# Granny_Safe_Power_Supply.net
KiCad netlist of a schematic drawn in EAGLE
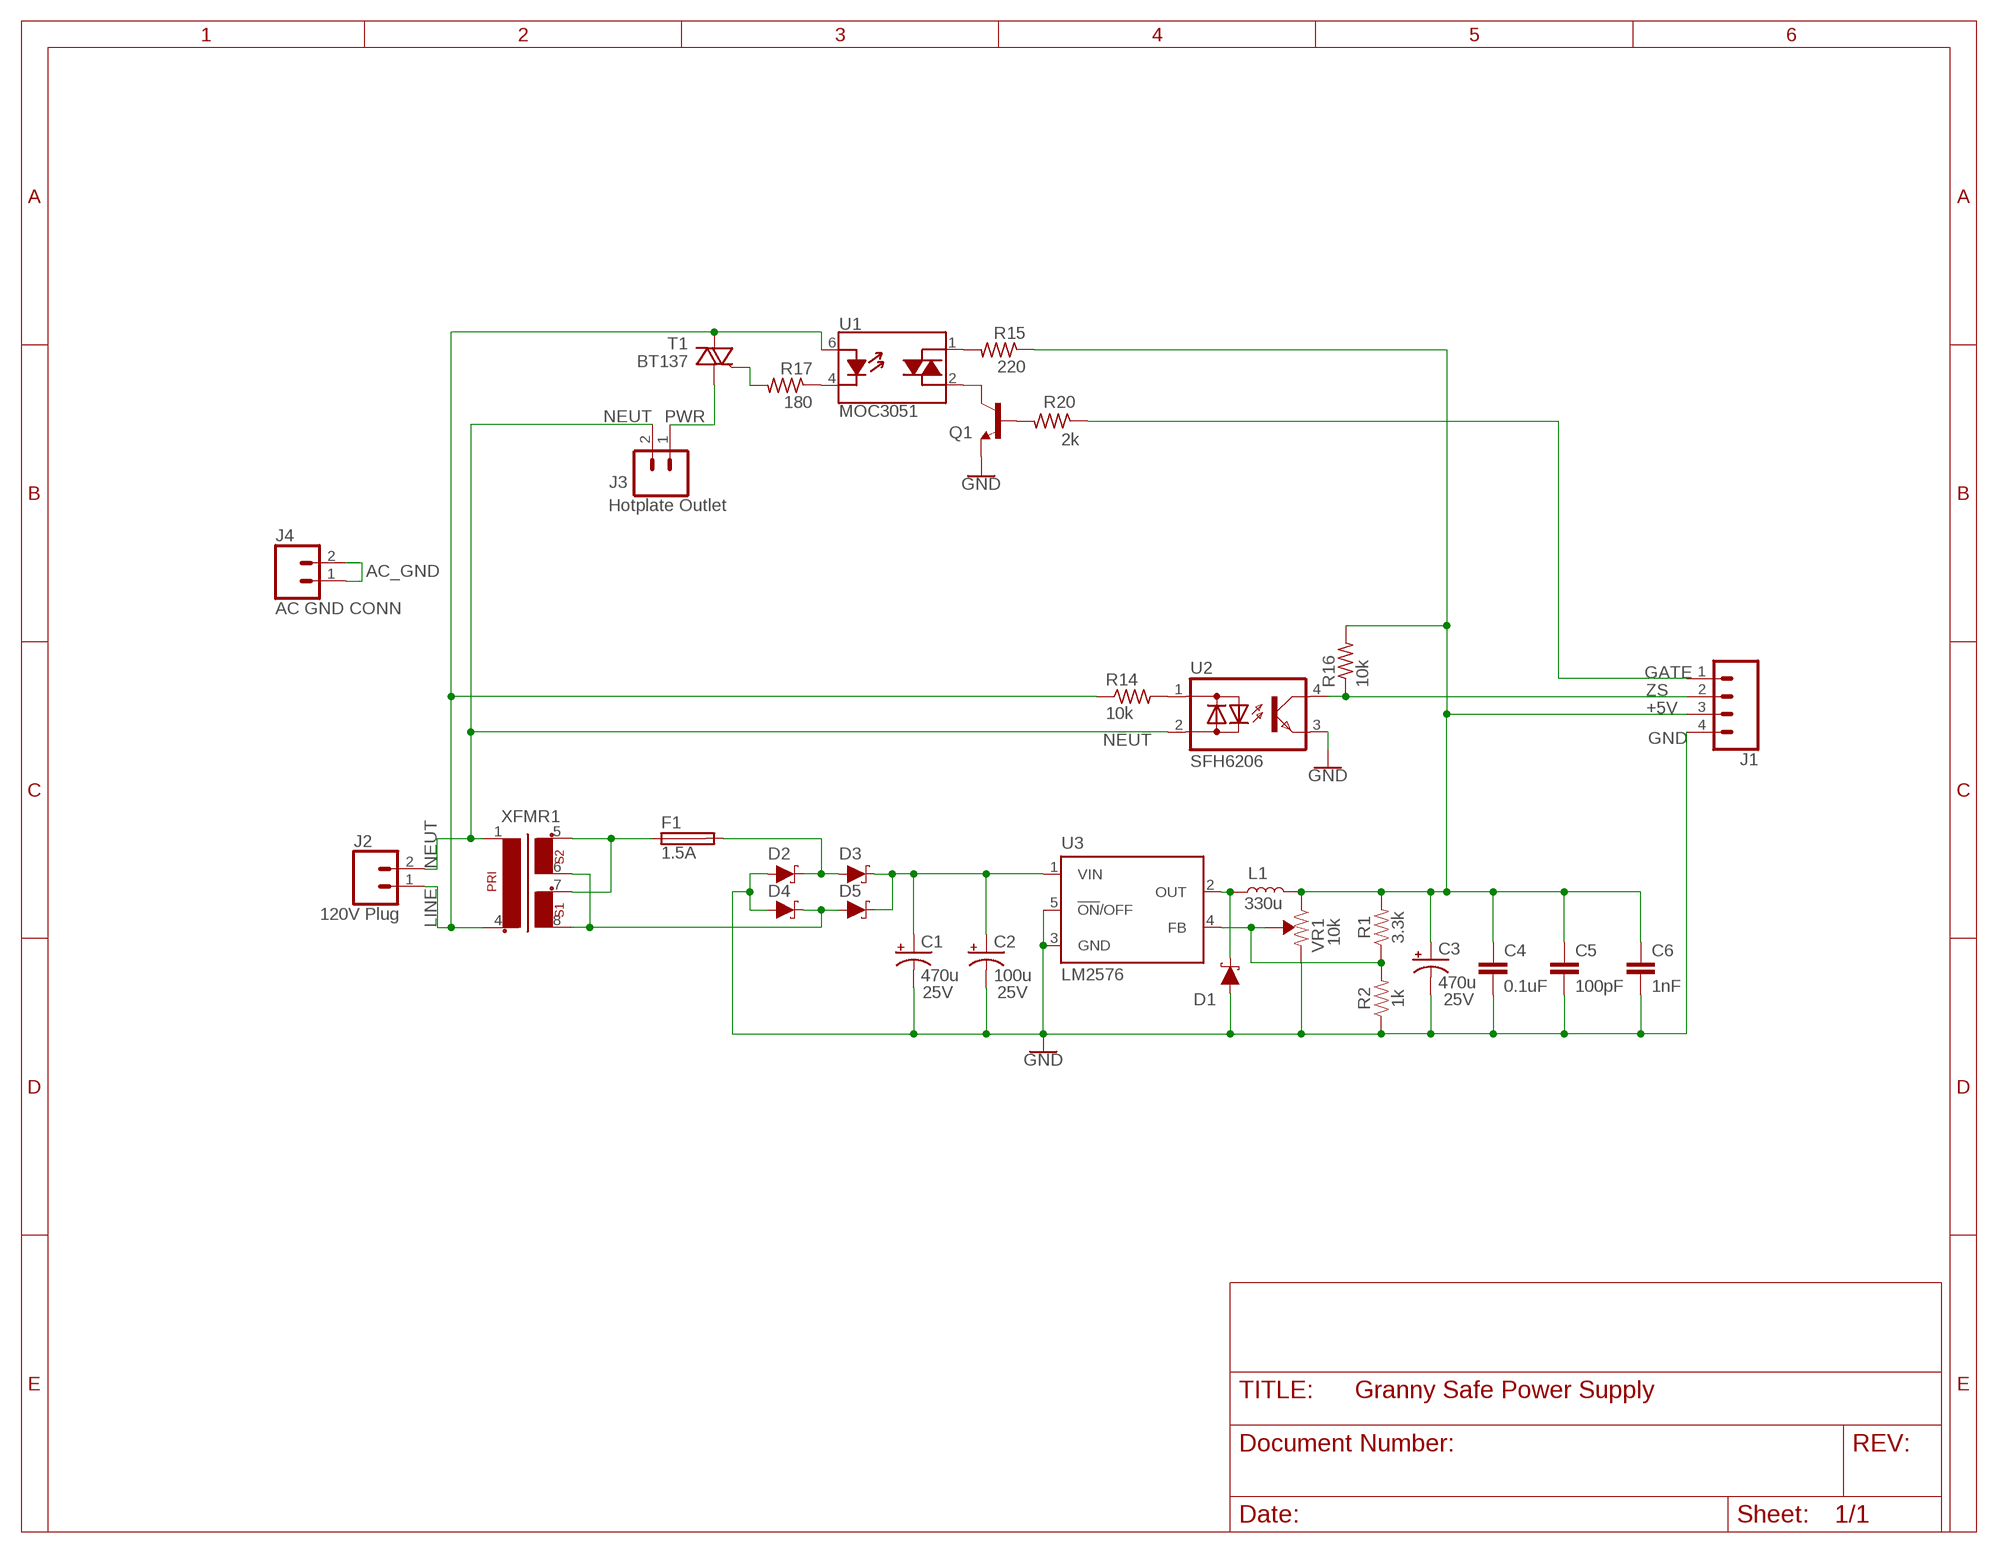
[diagram p0: schematic, sheet 1]

(export (version "E")
  (design (tool "Eeschema 10.0.6"))
  (components
    (comp (ref "C1")
      (value "470u")
      (footprint "eagle-import:E3,5-8")
      (libsource (lib "eagle-import") (part "CPOL-USE3.5-8"))
    )
    (comp (ref "C2")
      (value "100u")
      (footprint "eagle-import:E2-5")
      (libsource (lib "eagle-import") (part "CPOL-USE2-5"))
    )
    (comp (ref "C3")
      (value "470u")
      (footprint "eagle-import:E3,5-8")
      (libsource (lib "eagle-import") (part "CPOL-USE3.5-8"))
    )
    (comp (ref "C4")
      (value "0.1uF")
      (footprint "eagle-import:0603")
      (libsource (lib "eagle-import") (part "0.1UF-0603-25V-5%"))
    )
    (comp (ref "C5")
      (value "100pF")
      (footprint "eagle-import:0603")
      (libsource (lib "eagle-import") (part "100PF-0603-50V-5%"))
    )
    (comp (ref "C6")
      (value "1nF")
      (footprint "eagle-import:0603")
      (libsource (lib "eagle-import") (part "1.0NF/1000PF-0603-50V-10%"))
    )
    (comp (ref "D1")
      (value "DIODE-SCHOTTKY-B340A")
      (footprint "eagle-import:SMA-DIODE")
      (libsource (lib "eagle-import") (part "DIODE-SCHOTTKY-B340A"))
    )
    (comp (ref "D2")
      (value "DIODE-SCHOTTKY-B340A")
      (footprint "eagle-import:SMA-DIODE")
      (libsource (lib "eagle-import") (part "DIODE-SCHOTTKY-B340A"))
    )
    (comp (ref "D3")
      (value "DIODE-SCHOTTKY-B340A")
      (footprint "eagle-import:SMA-DIODE")
      (libsource (lib "eagle-import") (part "DIODE-SCHOTTKY-B340A"))
    )
    (comp (ref "D4")
      (value "DIODE-SCHOTTKY-B340A")
      (footprint "eagle-import:SMA-DIODE")
      (libsource (lib "eagle-import") (part "DIODE-SCHOTTKY-B340A"))
    )
    (comp (ref "D5")
      (value "DIODE-SCHOTTKY-B340A")
      (footprint "eagle-import:SMA-DIODE")
      (libsource (lib "eagle-import") (part "DIODE-SCHOTTKY-B340A"))
    )
    (comp (ref "F1")
      (value "1.5A")
      (footprint "eagle-import:TE5")
      (libsource (lib "eagle-import") (part "TE5"))
    )
    (comp (ref "IC1")
      (value "LM2596S")
      (footprint "eagle-import:TO263-5")
      (fields (field (name "MF") "NATIONAL SEMICONDUCTOR") (field (name "MPN") "LM2596S-ADJ/NOPB"))
      (libsource (lib "eagle-import") (part "LM2596S"))
    )
    (comp (ref "J1")
      (value "CONN_04")
      (footprint "eagle-import:1X04")
      (libsource (lib "eagle-import") (part "CONN_04"))
    )
    (comp (ref "J2")
      (value "120V Plug")
      (footprint "eagle-import:SCREWTERMINAL-5MM-2")
      (libsource (lib "eagle-import") (part "CONN_025MM"))
    )
    (comp (ref "J3")
      (value "Hotplate Outlet")
      (footprint "eagle-import:SCREWTERMINAL-5MM-2")
      (libsource (lib "eagle-import") (part "CONN_025MM"))
    )
    (comp (ref "J4")
      (value "AC GND CONN")
      (footprint "eagle-import:SCREWTERMINAL-5MM-2")
      (libsource (lib "eagle-import") (part "CONN_025MM"))
    )
    (comp (ref "L1")
      (value "INDUCTOR")
      (footprint "eagle-import:CR75")
      (libsource (lib "eagle-import") (part "INDUCTOR"))
    )
    (comp (ref "Q1")
      (value "2N3904")
      (footprint "eagle-import:SOT23-3")
      (libsource (lib "eagle-import") (part "TRANS_NPN-MMBTA42"))
    )
    (comp (ref "R1")
      (value "3.3k")
      (footprint "eagle-import:0603")
      (libsource (lib "eagle-import") (part "3.3KOHM-0603-1/10W-1%"))
    )
    (comp (ref "R2")
      (value "1k")
      (footprint "eagle-import:0603")
      (libsource (lib "eagle-import") (part "1KOHM-0603-1/10W-1%"))
    )
    (comp (ref "R14")
      (value "10k")
      (footprint "eagle-import:R0603")
      (libsource (lib "eagle-import") (part "R-US_R0603"))
    )
    (comp (ref "R15")
      (value "220")
      (footprint "eagle-import:R0603")
      (libsource (lib "eagle-import") (part "R-US_R0603"))
    )
    (comp (ref "R16")
      (value "10k")
      (footprint "eagle-import:R0603")
      (libsource (lib "eagle-import") (part "R-US_R0603"))
    )
    (comp (ref "R17")
      (value "180")
      (footprint "eagle-import:R0603")
      (libsource (lib "eagle-import") (part "R-US_R0603"))
    )
    (comp (ref "R20")
      (value "2k")
      (footprint "eagle-import:R0603")
      (libsource (lib "eagle-import") (part "R-US_R0603"))
    )
    (comp (ref "T1")
      (value "BT137")
      (footprint "eagle-import:TO220BV")
      (libsource (lib "eagle-import") (part "BT137"))
    )
    (comp (ref "U1")
      (value "MOC3051")
      (footprint "eagle-import:DIP8SMD")
      (libsource (lib "eagle-import") (part "MOC3051"))
    )
    (comp (ref "U2")
      (value "SFH6206")
      (footprint "eagle-import:DIL4-SMD")
      (fields (field (name "MF") "VISHAY/TELEFUNKEN") (field (name "MPN") "SFH6206-3"))
      (libsource (lib "eagle-import") (part "SFH6206"))
    )
    (comp (ref "VR1")
      (value "10k")
      (footprint "eagle-import:TRIMPOT-SMD-TC33X")
      (libsource (lib "eagle-import") (part "TRIMPOT-SMD-3MM-OPEN-1/10W-25%"))
    )
    (comp (ref "XFMR1")
      (value "EE20-2")
      (footprint "eagle-import:EE20-2")
      (libsource (lib "eagle-import") (part "EE20-2"))
    )
  )
  (nets
    (net (code "1") (name "/+5V") (class "Default")
      (node (ref "C3") (pin "+") (pinfunction "+_+") (pintype "passive"))
      (node (ref "C4") (pin "1") (pinfunction "1_1") (pintype "passive"))
      (node (ref "C5") (pin "1") (pinfunction "1_1") (pintype "passive"))
      (node (ref "C6") (pin "1") (pinfunction "1_1") (pintype "passive"))
      (node (ref "J1") (pin "3") (pinfunction "3_3") (pintype "passive"))
      (node (ref "L1") (pin "P$2") (pinfunction "2_P$2") (pintype "passive"))
      (node (ref "R1") (pin "2") (pinfunction "2_2") (pintype "passive"))
      (node (ref "R15") (pin "1") (pinfunction "1_1") (pintype "passive"))
      (node (ref "R16") (pin "2") (pinfunction "2_2") (pintype "passive"))
      (node (ref "VR1") (pin "1") (pinfunction "CW_1") (pintype "passive"))
    )
    (net (code "2") (name "/AC_GND") (class "Default")
      (node (ref "J4") (pin "1") (pinfunction "1_1") (pintype "passive"))
      (node (ref "J4") (pin "2") (pinfunction "2_2") (pintype "passive"))
    )
    (net (code "3") (name "/GATE") (class "Default")
      (node (ref "J1") (pin "1") (pinfunction "1_1") (pintype "passive"))
      (node (ref "R20") (pin "1") (pinfunction "1_1") (pintype "passive"))
    )
    (net (code "4") (name "/LINE") (class "Default")
      (node (ref "J2") (pin "1") (pinfunction "1_1") (pintype "passive"))
      (node (ref "R14") (pin "1") (pinfunction "1_1") (pintype "passive"))
      (node (ref "T1") (pin "T2") (pinfunction "A2_T2") (pintype "passive"))
      (node (ref "U1") (pin "6") (pinfunction "6_6") (pintype "bidirectional"))
      (node (ref "XFMR1") (pin "4") (pinfunction "2_4") (pintype "passive"))
    )
    (net (code "5") (name "/NEUT") (class "Default")
      (node (ref "J2") (pin "2") (pinfunction "2_2") (pintype "passive"))
      (node (ref "J3") (pin "2") (pinfunction "2_2") (pintype "passive"))
      (node (ref "U2") (pin "2") (pinfunction "AC2_2") (pintype "passive"))
      (node (ref "XFMR1") (pin "1") (pinfunction "1_1") (pintype "passive"))
    )
    (net (code "6") (name "/PWR") (class "Default")
      (node (ref "J3") (pin "1") (pinfunction "1_1") (pintype "passive"))
      (node (ref "T1") (pin "T1") (pinfunction "A1_T1") (pintype "passive"))
    )
    (net (code "7") (name "/ZS") (class "Default")
      (node (ref "J1") (pin "2") (pinfunction "2_2") (pintype "passive"))
      (node (ref "R16") (pin "1") (pinfunction "1_1") (pintype "passive"))
      (node (ref "U2") (pin "4") (pinfunction "C_4") (pintype "passive"))
    )
    (net (code "8") (name "GND") (class "Default")
      (node (ref "C1") (pin "-") (pinfunction "-_-") (pintype "passive"))
      (node (ref "C2") (pin "-") (pinfunction "-_-") (pintype "passive"))
      (node (ref "C3") (pin "-") (pinfunction "-_-") (pintype "passive"))
      (node (ref "C4") (pin "2") (pinfunction "2_2") (pintype "passive"))
      (node (ref "C5") (pin "2") (pinfunction "2_2") (pintype "passive"))
      (node (ref "C6") (pin "2") (pinfunction "2_2") (pintype "passive"))
      (node (ref "D1") (pin "A") (pinfunction "A_A") (pintype "passive"))
      (node (ref "D2") (pin "A") (pinfunction "A_A") (pintype "passive"))
      (node (ref "D4") (pin "A") (pinfunction "A_A") (pintype "passive"))
      (node (ref "IC1") (pin "3") (pinfunction "GND_3") (pintype "power_in"))
      (node (ref "IC1") (pin "5") (pinfunction "~{ON}/OFF_5") (pintype "input"))
      (node (ref "J1") (pin "4") (pinfunction "4_4") (pintype "passive"))
      (node (ref "Q1") (pin "2") (pinfunction "E_2") (pintype "passive"))
      (node (ref "R2") (pin "1") (pinfunction "1_1") (pintype "passive"))
      (node (ref "U2") (pin "3") (pinfunction "E_3") (pintype "passive"))
      (node (ref "VR1") (pin "3") (pinfunction "CCW_3") (pintype "passive"))
    )
    (net (code "9") (name "Net-(D2-PadC)") (class "Default")
      (node (ref "D2") (pin "C") (pinfunction "C_C") (pintype "passive"))
      (node (ref "D3") (pin "A") (pinfunction "A_A") (pintype "passive"))
      (node (ref "F1") (pin "2") (pinfunction "2_2") (pintype "passive"))
    )
    (net (code "10") (name "Net-(IC1-FB)") (class "Default")
      (node (ref "IC1") (pin "4") (pinfunction "FB_4") (pintype "input"))
      (node (ref "R1") (pin "1") (pinfunction "1_1") (pintype "passive"))
      (node (ref "R2") (pin "2") (pinfunction "2_2") (pintype "passive"))
      (node (ref "VR1") (pin "2") (pinfunction "WIPER_2") (pintype "passive"))
    )
    (net (code "11") (name "Net-(IC1-OUT)") (class "Default")
      (node (ref "D1") (pin "C") (pinfunction "C_C") (pintype "passive"))
      (node (ref "IC1") (pin "2") (pinfunction "OUT_2") (pintype "output"))
      (node (ref "L1") (pin "P$1") (pinfunction "1_P$1") (pintype "passive"))
    )
    (net (code "12") (name "Net-(IC1-VIN)") (class "Default")
      (node (ref "C1") (pin "+") (pinfunction "+_+") (pintype "passive"))
      (node (ref "C2") (pin "+") (pinfunction "+_+") (pintype "passive"))
      (node (ref "D3") (pin "C") (pinfunction "C_C") (pintype "passive"))
      (node (ref "D5") (pin "C") (pinfunction "C_C") (pintype "passive"))
      (node (ref "IC1") (pin "1") (pinfunction "VIN_1") (pintype "input"))
    )
    (net (code "13") (name "Net-(Q1-B)") (class "Default")
      (node (ref "Q1") (pin "1") (pinfunction "B_1") (pintype "passive"))
      (node (ref "R20") (pin "2") (pinfunction "2_2") (pintype "passive"))
    )
    (net (code "14") (name "Net-(Q1-C)") (class "Default")
      (node (ref "Q1") (pin "3") (pinfunction "C_3") (pintype "passive"))
      (node (ref "U1") (pin "2") (pinfunction "2_2") (pintype "bidirectional"))
    )
    (net (code "15") (name "Net-(R15-Pad2)") (class "Default")
      (node (ref "R15") (pin "2") (pinfunction "2_2") (pintype "passive"))
      (node (ref "U1") (pin "1") (pinfunction "1_1") (pintype "bidirectional"))
    )
    (net (code "16") (name "Net-(R17-Pad1)") (class "Default")
      (node (ref "R17") (pin "1") (pinfunction "1_1") (pintype "passive"))
      (node (ref "U1") (pin "4") (pinfunction "4_4") (pintype "bidirectional"))
    )
    (net (code "17") (name "Net-(R17-Pad2)") (class "Default")
      (node (ref "R17") (pin "2") (pinfunction "2_2") (pintype "passive"))
      (node (ref "T1") (pin "G") (pinfunction "G_G") (pintype "passive"))
    )
    (net (code "18") (name "Net-(U2-AC1)") (class "Default")
      (node (ref "R14") (pin "2") (pinfunction "2_2") (pintype "passive"))
      (node (ref "U2") (pin "1") (pinfunction "AC1_1") (pintype "passive"))
    )
    (net (code "19") (name "Net-(XFMR1-3)") (class "Default")
      (node (ref "D4") (pin "C") (pinfunction "C_C") (pintype "passive"))
      (node (ref "D5") (pin "A") (pinfunction "A_A") (pintype "passive"))
      (node (ref "XFMR1") (pin "6") (pinfunction "5_6") (pintype "passive"))
      (node (ref "XFMR1") (pin "8") (pinfunction "3_8") (pintype "passive"))
    )
    (net (code "20") (name "Net-(XFMR1-4)") (class "Default")
      (node (ref "F1") (pin "1") (pinfunction "1_1") (pintype "passive"))
      (node (ref "XFMR1") (pin "5") (pinfunction "6_5") (pintype "passive"))
      (node (ref "XFMR1") (pin "7") (pinfunction "4_7") (pintype "passive"))
    )
  )
)
